# OverCurrent_Protection_circuit.net
KiCad netlist of a schematic drawn in Altium Designer
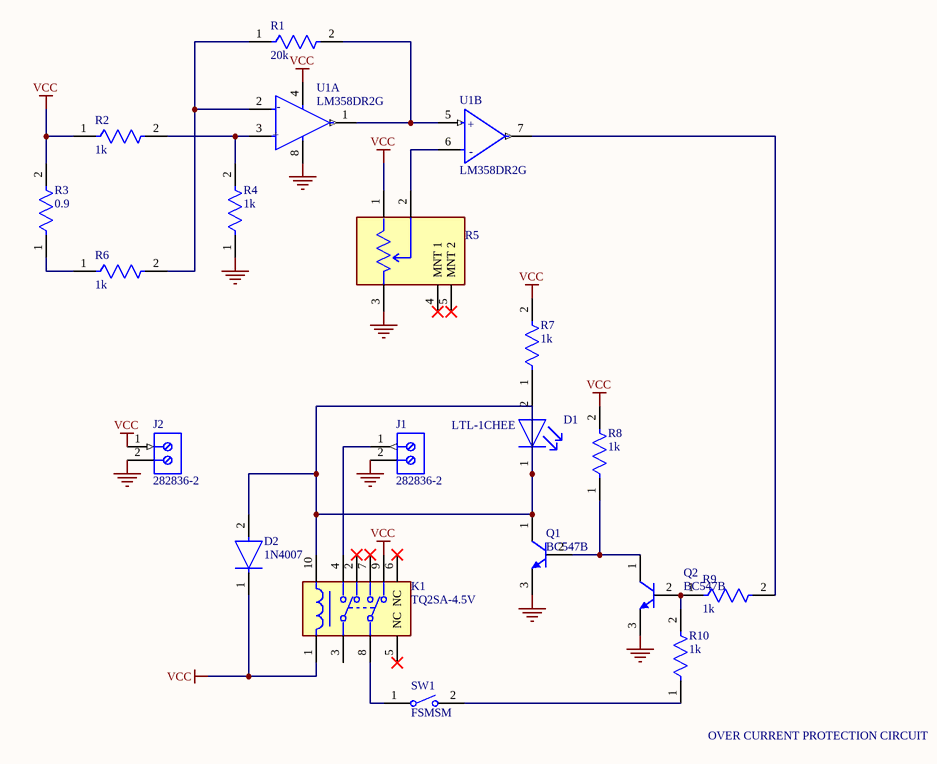
[diagram p0: OverCurrent Protection circuit.SchDoc]

(export (version "E")
  (design (tool "Eeschema 10.0.6"))
  (components
    (comp (ref "D1")
      (value "LTL-1CHEE")
      (footprint "FP-LTL-1CHEE-MFG")
      (description "LED RED CLEAR T/H")
      (libsource (lib "Altium Content Vault") (part "8706943c75ba83719d021d2fdc84c58"))
    )
    (comp (ref "D2")
      (value "1N4007")
      (footprint "FP-1N4007-MFG")
      (description "Rectifier diode 1000 V 1 A DO-41, ,")
      (fields
        (field (name "MANUFACTURER") "Diotec")
        (field (name "OCTOPART") "https://octopart.com/1n4007-diotec-4040411")
      )
      (libsource (lib "Altium Content Vault") (part "d7152d700b627762746794eb795d46e"))
    )
    (comp (ref "J1")
      (value "282836-2")
      (footprint "TECO-282836-2_V")
      (description "Female Header, Pitch 5 mm, 1 x 2 Position, Height 10 mm, Tail Length 3.5 mm, Rohs, Bulk")
      (fields (field (name "VOLTAGE") "300V") (field (name "MANUFACTURER") "TE Connectivity"))
      (libsource (lib "Altium Content Vault") (part "CN-1P-F-TB2"))
    )
    (comp (ref "J2")
      (value "282836-2")
      (footprint "TECO-282836-2_V")
      (description "Female Header, Pitch 5 mm, 1 x 2 Position, Height 10 mm, Tail Length 3.5 mm, Rohs, Bulk")
      (fields (field (name "VOLTAGE") "300V") (field (name "MANUFACTURER") "TE Connectivity"))
      (libsource (lib "Altium Content Vault") (part "CN-1P-F-TB2"))
    )
    (comp (ref "K1")
      (value "TQ2SA-4.5V")
      (footprint "FP-TQ2SA-4_5V-MFG")
      (description "TQ2SA-4.5V Electromechanical Relay DPDT 2A 4.5VDC 145Ohm Surface Mount")
      (libsource (lib "Altium Content Vault") (part "747507aa550a4604fd2742a07807ff2"))
    )
    (comp (ref "Q1")
      (value "BC547B")
      (footprint "ONSC-TO-92-3-29-11")
      (description "Amplifier Transistor, NPN Silicon, 3-Pin TO-92, Bulk Box")
      (fields (field (name "MANUFACTURER") "On Semiconductor"))
      (libsource (lib "Altium Content Vault") (part "ONSC-NPN-C1B2E3-3"))
    )
    (comp (ref "Q2")
      (value "BC547B")
      (footprint "ONSC-TO-92-3-29-11")
      (description "Amplifier Transistor, NPN Silicon, 3-Pin TO-92, Bulk Box")
      (fields (field (name "MANUFACTURER") "On Semiconductor"))
      (libsource (lib "Altium Content Vault") (part "ONSC-NPN-C1B2E3-3"))
    )
    (comp (ref "R1")
      (value "20k")
      (footprint "FP-CF14-MFG")
      (description "RES 7.5K OHM 1/4W 5% AXIAL")
      (fields (field (name "TOLERANCE") "5%"))
      (libsource (lib "Altium Content Vault") (part "1029c3af85768c4190bb7ad29bc67b5"))
    )
    (comp (ref "R2")
      (value "1k")
      (footprint "FP-CF14-MFG")
      (description "RES 7.5K OHM 1/4W 5% AXIAL")
      (fields (field (name "TOLERANCE") "5%"))
      (libsource (lib "Altium Content Vault") (part "1029c3af85768c4190bb7ad29bc67b5"))
    )
    (comp (ref "R3")
      (value "0.9")
      (footprint "FP-CF14-MFG")
      (description "RES 7.5K OHM 1/4W 5% AXIAL")
      (fields (field (name "TOLERANCE") "5%"))
      (libsource (lib "Altium Content Vault") (part "1029c3af85768c4190bb7ad29bc67b5"))
    )
    (comp (ref "R4")
      (value "1k")
      (footprint "FP-CF14-MFG")
      (description "RES 7.5K OHM 1/4W 5% AXIAL")
      (fields (field (name "TOLERANCE") "5%"))
      (libsource (lib "Altium Content Vault") (part "1029c3af85768c4190bb7ad29bc67b5"))
    )
    (comp (ref "R5")
      (value "PTV09A-4225F-B103")
      (footprint "FP-PTV09A-4-MFG")
      (description "POT 10K OHM 1/20W CARBON LINEAR")
      (fields (field (name "TOLERANCE") "20%"))
      (libsource (lib "Altium Content Vault") (part "705d11b747745a787204d796a5f3d12"))
    )
    (comp (ref "R6")
      (value "1k")
      (footprint "FP-CF14-MFG")
      (description "RES 7.5K OHM 1/4W 5% AXIAL")
      (fields (field (name "TOLERANCE") "5%"))
      (libsource (lib "Altium Content Vault") (part "1029c3af85768c4190bb7ad29bc67b5"))
    )
    (comp (ref "R7")
      (value "1k")
      (footprint "FP-CF14-MFG")
      (description "RES 7.5K OHM 1/4W 5% AXIAL")
      (fields (field (name "TOLERANCE") "5%"))
      (libsource (lib "Altium Content Vault") (part "1029c3af85768c4190bb7ad29bc67b5"))
    )
    (comp (ref "R8")
      (value "1k")
      (footprint "FP-CF14-MFG")
      (description "RES 7.5K OHM 1/4W 5% AXIAL")
      (fields (field (name "TOLERANCE") "5%"))
      (libsource (lib "Altium Content Vault") (part "1029c3af85768c4190bb7ad29bc67b5"))
    )
    (comp (ref "R9")
      (value "1k")
      (footprint "FP-CF14-MFG")
      (description "RES 7.5K OHM 1/4W 5% AXIAL")
      (fields (field (name "TOLERANCE") "5%"))
      (libsource (lib "Altium Content Vault") (part "1029c3af85768c4190bb7ad29bc67b5"))
    )
    (comp (ref "R10")
      (value "1k")
      (footprint "FP-CF14-MFG")
      (description "RES 7.5K OHM 1/4W 5% AXIAL")
      (fields (field (name "TOLERANCE") "5%"))
      (libsource (lib "Altium Content Vault") (part "1029c3af85768c4190bb7ad29bc67b5"))
    )
    (comp (ref "SW1")
      (value "FSMSM")
      (footprint "TECO-FSMSM-2_V")
      (description "FSMSM Push Button Switch, 50 mA, -35 to 85 degC, 2-Pin SMD, RoHS, Bulk")
      (fields (field (name "MANUFACTURER") "TE Connectivity"))
      (libsource (lib "Altium Content Vault") (part "SW-SPST-2_C"))
    )
    (comp (ref "U1")
      (value "LM358DR2G")
      (footprint "FP-751-07-IPC_C")
      (description "IC OPAMP GP 2 CIRCUIT 8SOIC")
      (libsource (lib "Altium Content Vault") (part "992a6607d1d88c80ee6b45e5ba6cb1b"))
    )
  )
  (nets
    (net (code "1") (name "GND") (class "Default")
      (node (ref "J1") (pin "2") (pinfunction "2_2") (pintype "passive"))
      (node (ref "J2") (pin "2") (pinfunction "2_2") (pintype "passive"))
      (node (ref "Q1") (pin "3") (pinfunction "E_3") (pintype "passive"))
      (node (ref "Q2") (pin "3") (pinfunction "E_3") (pintype "passive"))
      (node (ref "R4") (pin "1") (pinfunction "1_1") (pintype "passive"))
      (node (ref "R5") (pin "3") (pinfunction "3_3") (pintype "passive"))
      (node (ref "U1") (pin "8") (pinfunction "VCC_8") (pintype "power_in"))
    )
    (net (code "2") (name "Net-(D1-A)") (class "Default")
      (node (ref "D1") (pin "2") (pinfunction "A_2") (pintype "passive"))
      (node (ref "R7") (pin "1") (pinfunction "1_1") (pintype "passive"))
    )
    (net (code "3") (name "Net-(D1-C)") (class "Default")
      (node (ref "D1") (pin "1") (pinfunction "C_1") (pintype "passive"))
      (node (ref "D2") (pin "2") (pinfunction "A_2") (pintype "passive"))
      (node (ref "K1") (pin "10") (pinfunction "10_10") (pintype "passive"))
      (node (ref "Q1") (pin "1") (pinfunction "C_1") (pintype "passive"))
    )
    (net (code "4") (name "Net-(J1-Pad1)") (class "Default")
      (node (ref "J1") (pin "1") (pinfunction "1_1") (pintype "output"))
      (node (ref "K1") (pin "4") (pinfunction "4_4") (pintype "passive"))
    )
    (net (code "5") (name "Net-(K1-Pad8)") (class "Default")
      (node (ref "K1") (pin "8") (pinfunction "8_8") (pintype "passive"))
      (node (ref "SW1") (pin "1") (pinfunction "1_1") (pintype "passive"))
    )
    (net (code "6") (name "Net-(Q1-B)") (class "Default")
      (node (ref "Q1") (pin "2") (pinfunction "B_2") (pintype "passive"))
      (node (ref "Q2") (pin "1") (pinfunction "C_1") (pintype "passive"))
      (node (ref "R8") (pin "1") (pinfunction "1_1") (pintype "passive"))
    )
    (net (code "7") (name "Net-(Q2-B)") (class "Default")
      (node (ref "Q2") (pin "2") (pinfunction "B_2") (pintype "passive"))
      (node (ref "R10") (pin "2") (pinfunction "2_2") (pintype "passive"))
      (node (ref "R9") (pin "1") (pinfunction "1_1") (pintype "passive"))
    )
    (net (code "8") (name "Net-(R3-Pad1)") (class "Default")
      (node (ref "R3") (pin "1") (pinfunction "1_1") (pintype "passive"))
      (node (ref "R6") (pin "1") (pinfunction "1_1") (pintype "passive"))
    )
    (net (code "9") (name "Net-(R10-Pad1)") (class "Default")
      (node (ref "R10") (pin "1") (pinfunction "1_1") (pintype "passive"))
      (node (ref "SW1") (pin "2") (pinfunction "2_2") (pintype "passive"))
    )
    (net (code "10") (name "Net-(U1A-INPUT_A+)") (class "Default")
      (node (ref "R2") (pin "2") (pinfunction "2_2") (pintype "passive"))
      (node (ref "R4") (pin "2") (pinfunction "2_2") (pintype "passive"))
      (node (ref "U1") (pin "3") (pinfunction "INPUT_A+_3") (pintype "tri_state"))
    )
    (net (code "11") (name "Net-(U1A-INPUT_A-)") (class "Default")
      (node (ref "R1") (pin "1") (pinfunction "1_1") (pintype "passive"))
      (node (ref "R6") (pin "2") (pinfunction "2_2") (pintype "passive"))
      (node (ref "U1") (pin "2") (pinfunction "INPUT_A-_2") (pintype "tri_state"))
    )
    (net (code "12") (name "Net-(U1A-OUTPUT_A)") (class "Default")
      (node (ref "R1") (pin "2") (pinfunction "2_2") (pintype "passive"))
      (node (ref "U1") (pin "1") (pinfunction "OUTPUT_A_1") (pintype "output"))
      (node (ref "U1") (pin "5") (pinfunction "INPUT_B+_5") (pintype "input"))
    )
    (net (code "13") (name "Net-(U1B-INPUT_B-)") (class "Default")
      (node (ref "R5") (pin "2") (pinfunction "2_2") (pintype "passive"))
      (node (ref "U1") (pin "6") (pinfunction "INPUT_B-_6") (pintype "tri_state"))
    )
    (net (code "14") (name "Net-(U1B-OUTPUT_B)") (class "Default")
      (node (ref "R9") (pin "2") (pinfunction "2_2") (pintype "passive"))
      (node (ref "U1") (pin "7") (pinfunction "OUTPUT_B_7") (pintype "output"))
    )
    (net (code "15") (name "VCC") (class "Default")
      (node (ref "D2") (pin "1") (pinfunction "C_1") (pintype "passive"))
      (node (ref "J2") (pin "1") (pinfunction "1_1") (pintype "output"))
      (node (ref "K1") (pin "1") (pinfunction "1_1") (pintype "passive"))
      (node (ref "K1") (pin "9") (pinfunction "9_9") (pintype "passive"))
      (node (ref "R2") (pin "1") (pinfunction "1_1") (pintype "passive"))
      (node (ref "R3") (pin "2") (pinfunction "2_2") (pintype "passive"))
      (node (ref "R5") (pin "1") (pinfunction "1_1") (pintype "passive"))
      (node (ref "R7") (pin "2") (pinfunction "2_2") (pintype "passive"))
      (node (ref "R8") (pin "2") (pinfunction "2_2") (pintype "passive"))
      (node (ref "U1") (pin "4") (pinfunction "VEE/GND_4") (pintype "power_in"))
    )
    (net (code "16") (name "unconnected-(K1-NC-Pad5)") (class "Default")
      (node (ref "K1") (pin "5") (pinfunction "NC_5") (pintype "passive+no_connect"))
    )
    (net (code "17") (name "unconnected-(K1-NC-Pad6)") (class "Default")
      (node (ref "K1") (pin "6") (pinfunction "NC_6") (pintype "passive+no_connect"))
    )
    (net (code "18") (name "unconnected-(K1-Pad2)") (class "Default")
      (node (ref "K1") (pin "2") (pinfunction "2_2") (pintype "passive+no_connect"))
    )
    (net (code "19") (name "unconnected-(K1-Pad3)") (class "Default")
      (node (ref "K1") (pin "3") (pinfunction "3_3") (pintype "passive"))
    )
    (net (code "20") (name "unconnected-(K1-Pad7)") (class "Default")
      (node (ref "K1") (pin "7") (pinfunction "7_7") (pintype "passive+no_connect"))
    )
    (net (code "21") (name "unconnected-(R5-MNT_1-Pad4)") (class "Default")
      (node (ref "R5") (pin "4") (pinfunction "MNT_1_4") (pintype "passive+no_connect"))
    )
    (net (code "22") (name "unconnected-(R5-MNT_2-Pad5)") (class "Default")
      (node (ref "R5") (pin "5") (pinfunction "MNT_2_5") (pintype "passive+no_connect"))
    )
  )
)
